# Tstat.net
KiCad netlist of a schematic drawn in EAGLE
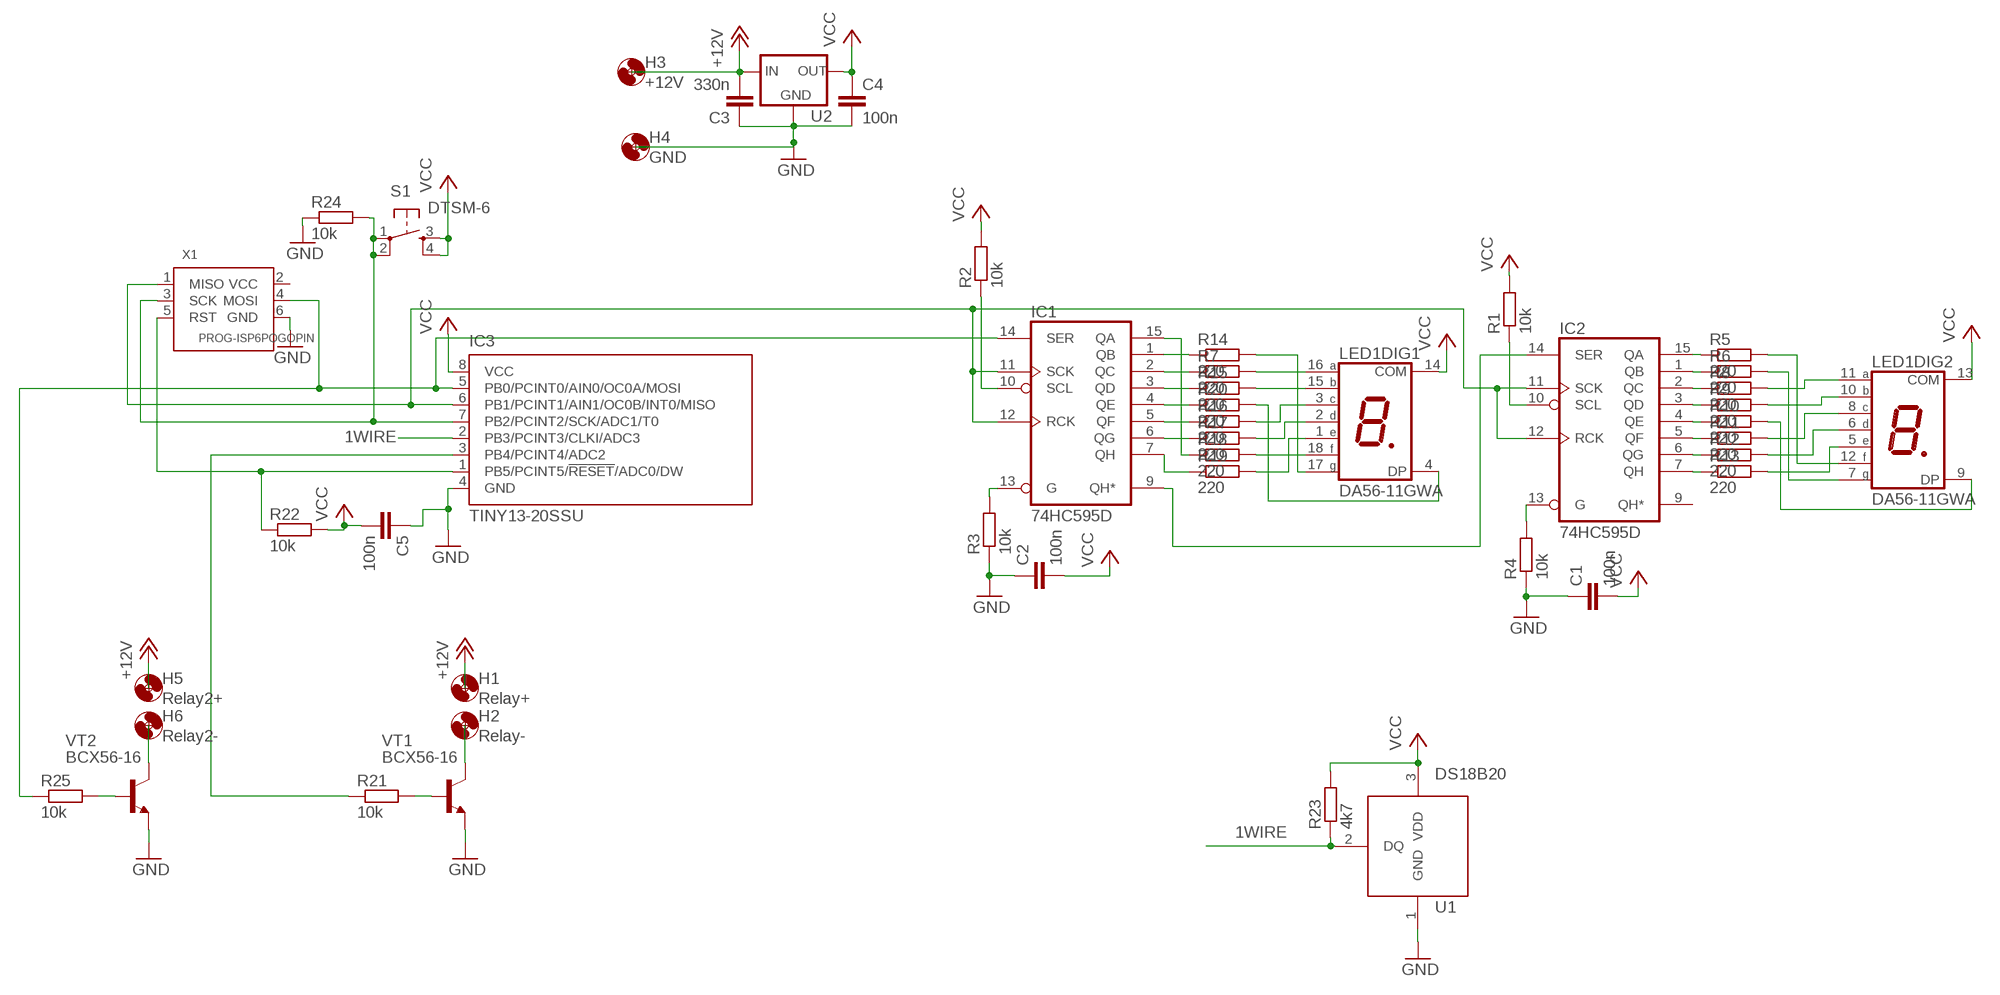
[diagram p0: schematic, sheet 1]

(export (version "E")
  (design (tool "Eeschema 10.0.6"))
  (components
    (comp (ref "C1")
      (value "100n")
      (footprint "eagle-import:C0805")
      (libsource (lib "eagle-import") (part "C-EUC0805"))
    )
    (comp (ref "C2")
      (value "100n")
      (footprint "eagle-import:C0805")
      (libsource (lib "eagle-import") (part "C-EUC0805"))
    )
    (comp (ref "C3")
      (value "330n")
      (footprint "eagle-import:C0805")
      (libsource (lib "eagle-import") (part "C-EUC0805"))
    )
    (comp (ref "C4")
      (value "100n")
      (footprint "eagle-import:C0805")
      (libsource (lib "eagle-import") (part "C-EUC0805"))
    )
    (comp (ref "C5")
      (value "100n")
      (footprint "eagle-import:C0805")
      (libsource (lib "eagle-import") (part "C-EUC0805"))
    )
    (comp (ref "H1")
      (value "Relay+")
      (footprint "eagle-import:3,0")
      (libsource (lib "eagle-import") (part "MOUNT-HOLE3.0"))
    )
    (comp (ref "H2")
      (value "Relay-")
      (footprint "eagle-import:3,0")
      (libsource (lib "eagle-import") (part "MOUNT-HOLE3.0"))
    )
    (comp (ref "H3")
      (value "+12V")
      (footprint "eagle-import:3,0")
      (libsource (lib "eagle-import") (part "MOUNT-HOLE3.0"))
    )
    (comp (ref "H4")
      (value "GND")
      (footprint "eagle-import:3,0")
      (libsource (lib "eagle-import") (part "MOUNT-HOLE3.0"))
    )
    (comp (ref "H5")
      (value "Relay2+")
      (footprint "eagle-import:3,0")
      (libsource (lib "eagle-import") (part "MOUNT-HOLE3.0"))
    )
    (comp (ref "H6")
      (value "Relay2-")
      (footprint "eagle-import:3,0")
      (libsource (lib "eagle-import") (part "MOUNT-HOLE3.0"))
    )
    (comp (ref "IC1")
      (value "74HC595D")
      (footprint "eagle-import:SO16")
      (libsource (lib "eagle-import") (part "74595DHC"))
    )
    (comp (ref "IC2")
      (value "74HC595D")
      (footprint "eagle-import:SO16")
      (libsource (lib "eagle-import") (part "74595DHC"))
    )
    (comp (ref "IC3")
      (value "TINY13-20SSU")
      (footprint "eagle-import:8S1")
      (fields (field (name "MPN") "ATTINY13-20SSU"))
      (libsource (lib "eagle-import") (part "TINY13SSU-20"))
    )
    (comp (ref "LED1")
      (value "DA56-11GWA")
      (footprint "eagle-import:DA56")
      (libsource (lib "eagle-import") (part "DA56-11GWA"))
    )
    (comp (ref "R1")
      (value "10k")
      (footprint "eagle-import:R0603")
      (libsource (lib "eagle-import") (part "R-EU_R0603"))
    )
    (comp (ref "R2")
      (value "10k")
      (footprint "eagle-import:R0603")
      (libsource (lib "eagle-import") (part "R-EU_R0603"))
    )
    (comp (ref "R3")
      (value "10k")
      (footprint "eagle-import:R0603")
      (libsource (lib "eagle-import") (part "R-EU_R0603"))
    )
    (comp (ref "R4")
      (value "10k")
      (footprint "eagle-import:R0603")
      (libsource (lib "eagle-import") (part "R-EU_R0603"))
    )
    (comp (ref "R5")
      (value "220")
      (footprint "eagle-import:R0603")
      (libsource (lib "eagle-import") (part "R-EU_R0603"))
    )
    (comp (ref "R6")
      (value "220")
      (footprint "eagle-import:R0603")
      (libsource (lib "eagle-import") (part "R-EU_R0603"))
    )
    (comp (ref "R7")
      (value "220")
      (footprint "eagle-import:R0603")
      (libsource (lib "eagle-import") (part "R-EU_R0603"))
    )
    (comp (ref "R8")
      (value "220")
      (footprint "eagle-import:R0603")
      (libsource (lib "eagle-import") (part "R-EU_R0603"))
    )
    (comp (ref "R9")
      (value "220")
      (footprint "eagle-import:R0603")
      (libsource (lib "eagle-import") (part "R-EU_R0603"))
    )
    (comp (ref "R10")
      (value "220")
      (footprint "eagle-import:R0603")
      (libsource (lib "eagle-import") (part "R-EU_R0603"))
    )
    (comp (ref "R11")
      (value "220")
      (footprint "eagle-import:R0603")
      (libsource (lib "eagle-import") (part "R-EU_R0603"))
    )
    (comp (ref "R12")
      (value "220")
      (footprint "eagle-import:R0603")
      (libsource (lib "eagle-import") (part "R-EU_R0603"))
    )
    (comp (ref "R13")
      (value "220")
      (footprint "eagle-import:R0603")
      (libsource (lib "eagle-import") (part "R-EU_R0603"))
    )
    (comp (ref "R14")
      (value "220")
      (footprint "eagle-import:R0603")
      (libsource (lib "eagle-import") (part "R-EU_R0603"))
    )
    (comp (ref "R15")
      (value "220")
      (footprint "eagle-import:R0603")
      (libsource (lib "eagle-import") (part "R-EU_R0603"))
    )
    (comp (ref "R16")
      (value "220")
      (footprint "eagle-import:R0603")
      (libsource (lib "eagle-import") (part "R-EU_R0603"))
    )
    (comp (ref "R17")
      (value "220")
      (footprint "eagle-import:R0603")
      (libsource (lib "eagle-import") (part "R-EU_R0603"))
    )
    (comp (ref "R18")
      (value "220")
      (footprint "eagle-import:R0603")
      (libsource (lib "eagle-import") (part "R-EU_R0603"))
    )
    (comp (ref "R19")
      (value "220")
      (footprint "eagle-import:R0603")
      (libsource (lib "eagle-import") (part "R-EU_R0603"))
    )
    (comp (ref "R20")
      (value "220")
      (footprint "eagle-import:R0603")
      (libsource (lib "eagle-import") (part "R-EU_R0603"))
    )
    (comp (ref "R21")
      (value "10k")
      (footprint "eagle-import:R0603")
      (libsource (lib "eagle-import") (part "R-EU_R0603"))
    )
    (comp (ref "R22")
      (value "10k")
      (footprint "eagle-import:R0603")
      (libsource (lib "eagle-import") (part "R-EU_R0603"))
    )
    (comp (ref "R23")
      (value "4k7")
      (footprint "eagle-import:R0603")
      (libsource (lib "eagle-import") (part "R-EU_R0603"))
    )
    (comp (ref "R24")
      (value "10k")
      (footprint "eagle-import:R0603")
      (libsource (lib "eagle-import") (part "R-EU_R0603"))
    )
    (comp (ref "R25")
      (value "10k")
      (footprint "eagle-import:R0603")
      (libsource (lib "eagle-import") (part "R-EU_R0603"))
    )
    (comp (ref "S1")
      (value "DTSM-6")
      (footprint "eagle-import:DTSM-6")
      (libsource (lib "eagle-import") (part "DTSM-6"))
    )
    (comp (ref "U1")
      (value "DS18B20")
      (footprint "eagle-import:TO92")
      (libsource (lib "eagle-import") (part "DS18B20"))
    )
    (comp (ref "U2")
      (value "L78XX/TO263")
      (footprint "eagle-import:TO263")
      (libsource (lib "eagle-import") (part "L78XX/TO263"))
    )
    (comp (ref "VT1")
      (value "BCX56-16")
      (footprint "eagle-import:SOT89-BCE")
      (libsource (lib "eagle-import") (part "BCX56-16"))
    )
    (comp (ref "VT2")
      (value "BCX56-16")
      (footprint "eagle-import:SOT89-BCE")
      (libsource (lib "eagle-import") (part "BCX56-16"))
    )
    (comp (ref "X1")
      (value "PROG-ISP6POGOPIN")
      (footprint "eagle-import:PROG_POGOPIN")
      (libsource (lib "eagle-import") (part "PROG-ISP6POGOPIN"))
    )
  )
  (nets
    (net (code "1") (name "+12V") (class "Default")
      (node (ref "C3") (pin "2") (pinfunction "2_2") (pintype "passive"))
      (node (ref "H1") (pin "P$1") (pinfunction "P$1_P$1") (pintype "bidirectional"))
      (node (ref "H3") (pin "P$1") (pinfunction "P$1_P$1") (pintype "bidirectional"))
      (node (ref "H5") (pin "P$1") (pinfunction "P$1_P$1") (pintype "bidirectional"))
      (node (ref "U2") (pin "1") (pinfunction "IN_1") (pintype "input"))
    )
    (net (code "2") (name "/1WIRE") (class "Default")
      (node (ref "IC3") (pin "2") (pinfunction "PB3/PCINT3/CLKI/ADC3_2") (pintype "bidirectional"))
      (node (ref "R23") (pin "1") (pinfunction "1_1") (pintype "passive"))
      (node (ref "U1") (pin "2") (pinfunction "DQ_2") (pintype "bidirectional"))
    )
    (net (code "3") (name "GND") (class "Default")
      (node (ref "C1") (pin "1") (pinfunction "1_1") (pintype "passive"))
      (node (ref "C2") (pin "1") (pinfunction "1_1") (pintype "passive"))
      (node (ref "C3") (pin "1") (pinfunction "1_1") (pintype "passive"))
      (node (ref "C4") (pin "2") (pinfunction "2_2") (pintype "passive"))
      (node (ref "C5") (pin "1") (pinfunction "1_1") (pintype "passive"))
      (node (ref "H4") (pin "P$1") (pinfunction "P$1_P$1") (pintype "bidirectional"))
      (node (ref "IC3") (pin "4") (pinfunction "GND_4") (pintype "power_in"))
      (node (ref "R24") (pin "1") (pinfunction "1_1") (pintype "passive"))
      (node (ref "R3") (pin "1") (pinfunction "1_1") (pintype "passive"))
      (node (ref "R4") (pin "1") (pinfunction "1_1") (pintype "passive"))
      (node (ref "U1") (pin "1") (pinfunction "GND_1") (pintype "power_in"))
      (node (ref "U2") (pin "3") (pinfunction "GND_3") (pintype "input"))
      (node (ref "VT1") (pin "E") (pinfunction "E_E") (pintype "passive"))
      (node (ref "VT2") (pin "E") (pinfunction "E_E") (pintype "passive"))
      (node (ref "X1") (pin "6") (pinfunction "GND_6") (pintype "bidirectional"))
    )
    (net (code "4") (name "Net-(H2-PadP$1)") (class "Default")
      (node (ref "H2") (pin "P$1") (pinfunction "P$1_P$1") (pintype "bidirectional"))
      (node (ref "VT1") (pin "C") (pinfunction "C_C") (pintype "passive"))
      (node (ref "VT1") (pin "C@1") (pinfunction "C_C@1") (pintype "passive"))
    )
    (net (code "5") (name "Net-(H6-PadP$1)") (class "Default")
      (node (ref "H6") (pin "P$1") (pinfunction "P$1_P$1") (pintype "bidirectional"))
      (node (ref "VT2") (pin "C") (pinfunction "C_C") (pintype "passive"))
      (node (ref "VT2") (pin "C@1") (pinfunction "C_C@1") (pintype "passive"))
    )
    (net (code "6") (name "Net-(IC1A-G)") (class "Default")
      (node (ref "IC1") (pin "13") (pinfunction "G_13") (pintype "input"))
      (node (ref "R3") (pin "2") (pinfunction "2_2") (pintype "passive"))
    )
    (net (code "7") (name "Net-(IC1A-QA)") (class "Default")
      (node (ref "IC1") (pin "15") (pinfunction "QA_15") (pintype "tri_state"))
      (node (ref "R18") (pin "1") (pinfunction "1_1") (pintype "passive"))
    )
    (net (code "8") (name "Net-(IC1A-QB)") (class "Default")
      (node (ref "IC1") (pin "1") (pinfunction "QB_1") (pintype "tri_state"))
      (node (ref "R14") (pin "1") (pinfunction "1_1") (pintype "passive"))
    )
    (net (code "9") (name "Net-(IC1A-QC)") (class "Default")
      (node (ref "IC1") (pin "2") (pinfunction "QC_2") (pintype "tri_state"))
      (node (ref "R7") (pin "1") (pinfunction "1_1") (pintype "passive"))
    )
    (net (code "10") (name "Net-(IC1A-QD)") (class "Default")
      (node (ref "IC1") (pin "3") (pinfunction "QD_3") (pintype "tri_state"))
      (node (ref "R15") (pin "1") (pinfunction "1_1") (pintype "passive"))
    )
    (net (code "11") (name "Net-(IC1A-QE)") (class "Default")
      (node (ref "IC1") (pin "4") (pinfunction "QE_4") (pintype "tri_state"))
      (node (ref "R20") (pin "1") (pinfunction "1_1") (pintype "passive"))
    )
    (net (code "12") (name "Net-(IC1A-QF)") (class "Default")
      (node (ref "IC1") (pin "5") (pinfunction "QF_5") (pintype "tri_state"))
      (node (ref "R16") (pin "1") (pinfunction "1_1") (pintype "passive"))
    )
    (net (code "13") (name "Net-(IC1A-QG)") (class "Default")
      (node (ref "IC1") (pin "6") (pinfunction "QG_6") (pintype "tri_state"))
      (node (ref "R17") (pin "1") (pinfunction "1_1") (pintype "passive"))
    )
    (net (code "14") (name "Net-(IC1A-QH)") (class "Default")
      (node (ref "IC1") (pin "7") (pinfunction "QH_7") (pintype "tri_state"))
      (node (ref "R19") (pin "1") (pinfunction "1_1") (pintype "passive"))
    )
    (net (code "15") (name "Net-(IC1A-QH*)") (class "Default")
      (node (ref "IC1") (pin "9") (pinfunction "QH*_9") (pintype "tri_state"))
      (node (ref "IC2") (pin "14") (pinfunction "SER_14") (pintype "input"))
    )
    (net (code "16") (name "Net-(IC1A-RCK)") (class "Default")
      (node (ref "IC1") (pin "11") (pinfunction "SCK_11") (pintype "input"))
      (node (ref "IC1") (pin "12") (pinfunction "RCK_12") (pintype "input"))
      (node (ref "IC2") (pin "11") (pinfunction "SCK_11") (pintype "input"))
      (node (ref "IC2") (pin "12") (pinfunction "RCK_12") (pintype "input"))
      (node (ref "IC3") (pin "6") (pinfunction "PB1/PCINT1/AIN1/OC0B/INT0/MISO_6") (pintype "bidirectional"))
      (node (ref "X1") (pin "1") (pinfunction "MISO_1") (pintype "bidirectional"))
    )
    (net (code "17") (name "Net-(IC1A-SCL)") (class "Default")
      (node (ref "IC1") (pin "10") (pinfunction "SCL_10") (pintype "input"))
      (node (ref "R2") (pin "1") (pinfunction "1_1") (pintype "passive"))
    )
    (net (code "18") (name "Net-(IC1A-SER)") (class "Default")
      (node (ref "IC1") (pin "14") (pinfunction "SER_14") (pintype "input"))
      (node (ref "IC3") (pin "5") (pinfunction "PB0/PCINT0/AIN0/OC0A/MOSI_5") (pintype "bidirectional"))
      (node (ref "R25") (pin "1") (pinfunction "1_1") (pintype "passive"))
      (node (ref "X1") (pin "4") (pinfunction "MOSI_4") (pintype "bidirectional"))
    )
    (net (code "19") (name "Net-(IC2A-G)") (class "Default")
      (node (ref "IC2") (pin "13") (pinfunction "G_13") (pintype "input"))
      (node (ref "R4") (pin "2") (pinfunction "2_2") (pintype "passive"))
    )
    (net (code "20") (name "Net-(IC2A-QA)") (class "Default")
      (node (ref "IC2") (pin "15") (pinfunction "QA_15") (pintype "tri_state"))
      (node (ref "R5") (pin "1") (pinfunction "1_1") (pintype "passive"))
    )
    (net (code "21") (name "Net-(IC2A-QB)") (class "Default")
      (node (ref "IC2") (pin "1") (pinfunction "QB_1") (pintype "tri_state"))
      (node (ref "R6") (pin "1") (pinfunction "1_1") (pintype "passive"))
    )
    (net (code "22") (name "Net-(IC2A-QC)") (class "Default")
      (node (ref "IC2") (pin "2") (pinfunction "QC_2") (pintype "tri_state"))
      (node (ref "R8") (pin "1") (pinfunction "1_1") (pintype "passive"))
    )
    (net (code "23") (name "Net-(IC2A-QD)") (class "Default")
      (node (ref "IC2") (pin "3") (pinfunction "QD_3") (pintype "tri_state"))
      (node (ref "R9") (pin "1") (pinfunction "1_1") (pintype "passive"))
    )
    (net (code "24") (name "Net-(IC2A-QE)") (class "Default")
      (node (ref "IC2") (pin "4") (pinfunction "QE_4") (pintype "tri_state"))
      (node (ref "R10") (pin "1") (pinfunction "1_1") (pintype "passive"))
    )
    (net (code "25") (name "Net-(IC2A-QF)") (class "Default")
      (node (ref "IC2") (pin "5") (pinfunction "QF_5") (pintype "tri_state"))
      (node (ref "R11") (pin "1") (pinfunction "1_1") (pintype "passive"))
    )
    (net (code "26") (name "Net-(IC2A-QG)") (class "Default")
      (node (ref "IC2") (pin "6") (pinfunction "QG_6") (pintype "tri_state"))
      (node (ref "R12") (pin "1") (pinfunction "1_1") (pintype "passive"))
    )
    (net (code "27") (name "Net-(IC2A-QH)") (class "Default")
      (node (ref "IC2") (pin "7") (pinfunction "QH_7") (pintype "tri_state"))
      (node (ref "R13") (pin "1") (pinfunction "1_1") (pintype "passive"))
    )
    (net (code "28") (name "Net-(IC2A-SCL)") (class "Default")
      (node (ref "IC2") (pin "10") (pinfunction "SCL_10") (pintype "input"))
      (node (ref "R1") (pin "1") (pinfunction "1_1") (pintype "passive"))
    )
    (net (code "29") (name "Net-(IC3-PB2{slash}PCINT2{slash}SCK{slash}ADC1{slash}T0)") (class "Default")
      (node (ref "IC3") (pin "7") (pinfunction "PB2/PCINT2/SCK/ADC1/T0_7") (pintype "bidirectional"))
      (node (ref "R24") (pin "2") (pinfunction "2_2") (pintype "passive"))
      (node (ref "S1") (pin "1") (pinfunction "1_1") (pintype "passive"))
      (node (ref "S1") (pin "2") (pinfunction "2_2") (pintype "passive"))
      (node (ref "X1") (pin "3") (pinfunction "SCK_3") (pintype "bidirectional"))
    )
    (net (code "30") (name "Net-(IC3-PB4{slash}PCINT4{slash}ADC2)") (class "Default")
      (node (ref "IC3") (pin "3") (pinfunction "PB4/PCINT4/ADC2_3") (pintype "bidirectional"))
      (node (ref "R21") (pin "1") (pinfunction "1_1") (pintype "passive"))
    )
    (net (code "31") (name "Net-(IC3-PB5{slash}PCINT5{slash}~{RESET}{slash}ADC0{slash}DW)") (class "Default")
      (node (ref "IC3") (pin "1") (pinfunction "PB5/PCINT5/~{RESET}/ADC0/DW_1") (pintype "bidirectional"))
      (node (ref "R22") (pin "1") (pinfunction "1_1") (pintype "passive"))
      (node (ref "X1") (pin "5") (pinfunction "RST_5") (pintype "bidirectional"))
    )
    (net (code "32") (name "Net-(LED1A-A)") (class "Default")
      (node (ref "LED1") (pin "16") (pinfunction "A_16") (pintype "passive"))
      (node (ref "R7") (pin "2") (pinfunction "2_2") (pintype "passive"))
    )
    (net (code "33") (name "Net-(LED1A-B)") (class "Default")
      (node (ref "LED1") (pin "15") (pinfunction "B_15") (pintype "passive"))
      (node (ref "R15") (pin "2") (pinfunction "2_2") (pintype "passive"))
    )
    (net (code "34") (name "Net-(LED1A-C)") (class "Default")
      (node (ref "LED1") (pin "3") (pinfunction "C_3") (pintype "passive"))
      (node (ref "R16") (pin "2") (pinfunction "2_2") (pintype "passive"))
    )
    (net (code "35") (name "Net-(LED1A-D)") (class "Default")
      (node (ref "LED1") (pin "2") (pinfunction "D_2") (pintype "passive"))
      (node (ref "R17") (pin "2") (pinfunction "2_2") (pintype "passive"))
    )
    (net (code "36") (name "Net-(LED1A-DP)") (class "Default")
      (node (ref "LED1") (pin "4") (pinfunction "DP_4") (pintype "passive"))
      (node (ref "R20") (pin "2") (pinfunction "2_2") (pintype "passive"))
    )
    (net (code "37") (name "Net-(LED1A-E)") (class "Default")
      (node (ref "LED1") (pin "1") (pinfunction "E_1") (pintype "passive"))
      (node (ref "R19") (pin "2") (pinfunction "2_2") (pintype "passive"))
    )
    (net (code "38") (name "Net-(LED1A-F)") (class "Default")
      (node (ref "LED1") (pin "18") (pinfunction "F_18") (pintype "passive"))
      (node (ref "R18") (pin "2") (pinfunction "2_2") (pintype "passive"))
    )
    (net (code "39") (name "Net-(LED1A-G)") (class "Default")
      (node (ref "LED1") (pin "17") (pinfunction "G_17") (pintype "passive"))
      (node (ref "R14") (pin "2") (pinfunction "2_2") (pintype "passive"))
    )
    (net (code "40") (name "Net-(LED1B-A)") (class "Default")
      (node (ref "LED1") (pin "11") (pinfunction "A_11") (pintype "passive"))
      (node (ref "R8") (pin "2") (pinfunction "2_2") (pintype "passive"))
    )
    (net (code "41") (name "Net-(LED1B-B)") (class "Default")
      (node (ref "LED1") (pin "10") (pinfunction "B_10") (pintype "passive"))
      (node (ref "R9") (pin "2") (pinfunction "2_2") (pintype "passive"))
    )
    (net (code "42") (name "Net-(LED1B-C)") (class "Default")
      (node (ref "LED1") (pin "8") (pinfunction "C_8") (pintype "passive"))
      (node (ref "R11") (pin "2") (pinfunction "2_2") (pintype "passive"))
    )
    (net (code "43") (name "Net-(LED1B-D)") (class "Default")
      (node (ref "LED1") (pin "6") (pinfunction "D_6") (pintype "passive"))
      (node (ref "R12") (pin "2") (pinfunction "2_2") (pintype "passive"))
    )
    (net (code "44") (name "Net-(LED1B-DP)") (class "Default")
      (node (ref "LED1") (pin "9") (pinfunction "DP_9") (pintype "passive"))
      (node (ref "R10") (pin "2") (pinfunction "2_2") (pintype "passive"))
    )
    (net (code "45") (name "Net-(LED1B-E)") (class "Default")
      (node (ref "LED1") (pin "5") (pinfunction "E_5") (pintype "passive"))
      (node (ref "R13") (pin "2") (pinfunction "2_2") (pintype "passive"))
    )
    (net (code "46") (name "Net-(LED1B-F)") (class "Default")
      (node (ref "LED1") (pin "12") (pinfunction "F_12") (pintype "passive"))
      (node (ref "R5") (pin "2") (pinfunction "2_2") (pintype "passive"))
    )
    (net (code "47") (name "Net-(LED1B-G)") (class "Default")
      (node (ref "LED1") (pin "7") (pinfunction "G_7") (pintype "passive"))
      (node (ref "R6") (pin "2") (pinfunction "2_2") (pintype "passive"))
    )
    (net (code "48") (name "Net-(R21-Pad2)") (class "Default")
      (node (ref "R21") (pin "2") (pinfunction "2_2") (pintype "passive"))
      (node (ref "VT1") (pin "B") (pinfunction "B_B") (pintype "passive"))
    )
    (net (code "49") (name "Net-(R25-Pad2)") (class "Default")
      (node (ref "R25") (pin "2") (pinfunction "2_2") (pintype "passive"))
      (node (ref "VT2") (pin "B") (pinfunction "B_B") (pintype "passive"))
    )
    (net (code "50") (name "VCC") (class "Default")
      (node (ref "C1") (pin "2") (pinfunction "2_2") (pintype "passive"))
      (node (ref "C2") (pin "2") (pinfunction "2_2") (pintype "passive"))
      (node (ref "C4") (pin "1") (pinfunction "1_1") (pintype "passive"))
      (node (ref "C5") (pin "2") (pinfunction "2_2") (pintype "passive"))
      (node (ref "IC3") (pin "8") (pinfunction "VCC_8") (pintype "power_in"))
      (node (ref "LED1") (pin "13") (pinfunction "COM_13") (pintype "passive"))
      (node (ref "LED1") (pin "14") (pinfunction "COM_14") (pintype "passive"))
      (node (ref "R1") (pin "2") (pinfunction "2_2") (pintype "passive"))
      (node (ref "R2") (pin "2") (pinfunction "2_2") (pintype "passive"))
      (node (ref "R22") (pin "2") (pinfunction "2_2") (pintype "passive"))
      (node (ref "R23") (pin "2") (pinfunction "2_2") (pintype "passive"))
      (node (ref "S1") (pin "3") (pinfunction "3_3") (pintype "passive"))
      (node (ref "S1") (pin "4") (pinfunction "4_4") (pintype "passive"))
      (node (ref "U1") (pin "3") (pinfunction "VDD_3") (pintype "power_in"))
      (node (ref "U2") (pin "2") (pinfunction "OUT_2") (pintype "passive"))
    )
    (net (code "51") (name "unconnected-(IC2A-QH*-Pad9)") (class "Default")
      (node (ref "IC2") (pin "9") (pinfunction "QH*_9") (pintype "tri_state"))
    )
    (net (code "52") (name "unconnected-(X1-VCC-Pad2)") (class "Default")
      (node (ref "X1") (pin "2") (pinfunction "VCC_2") (pintype "bidirectional"))
    )
  )
)
